# HSDL-9100.net
KiCad netlist of a schematic drawn in EAGLE
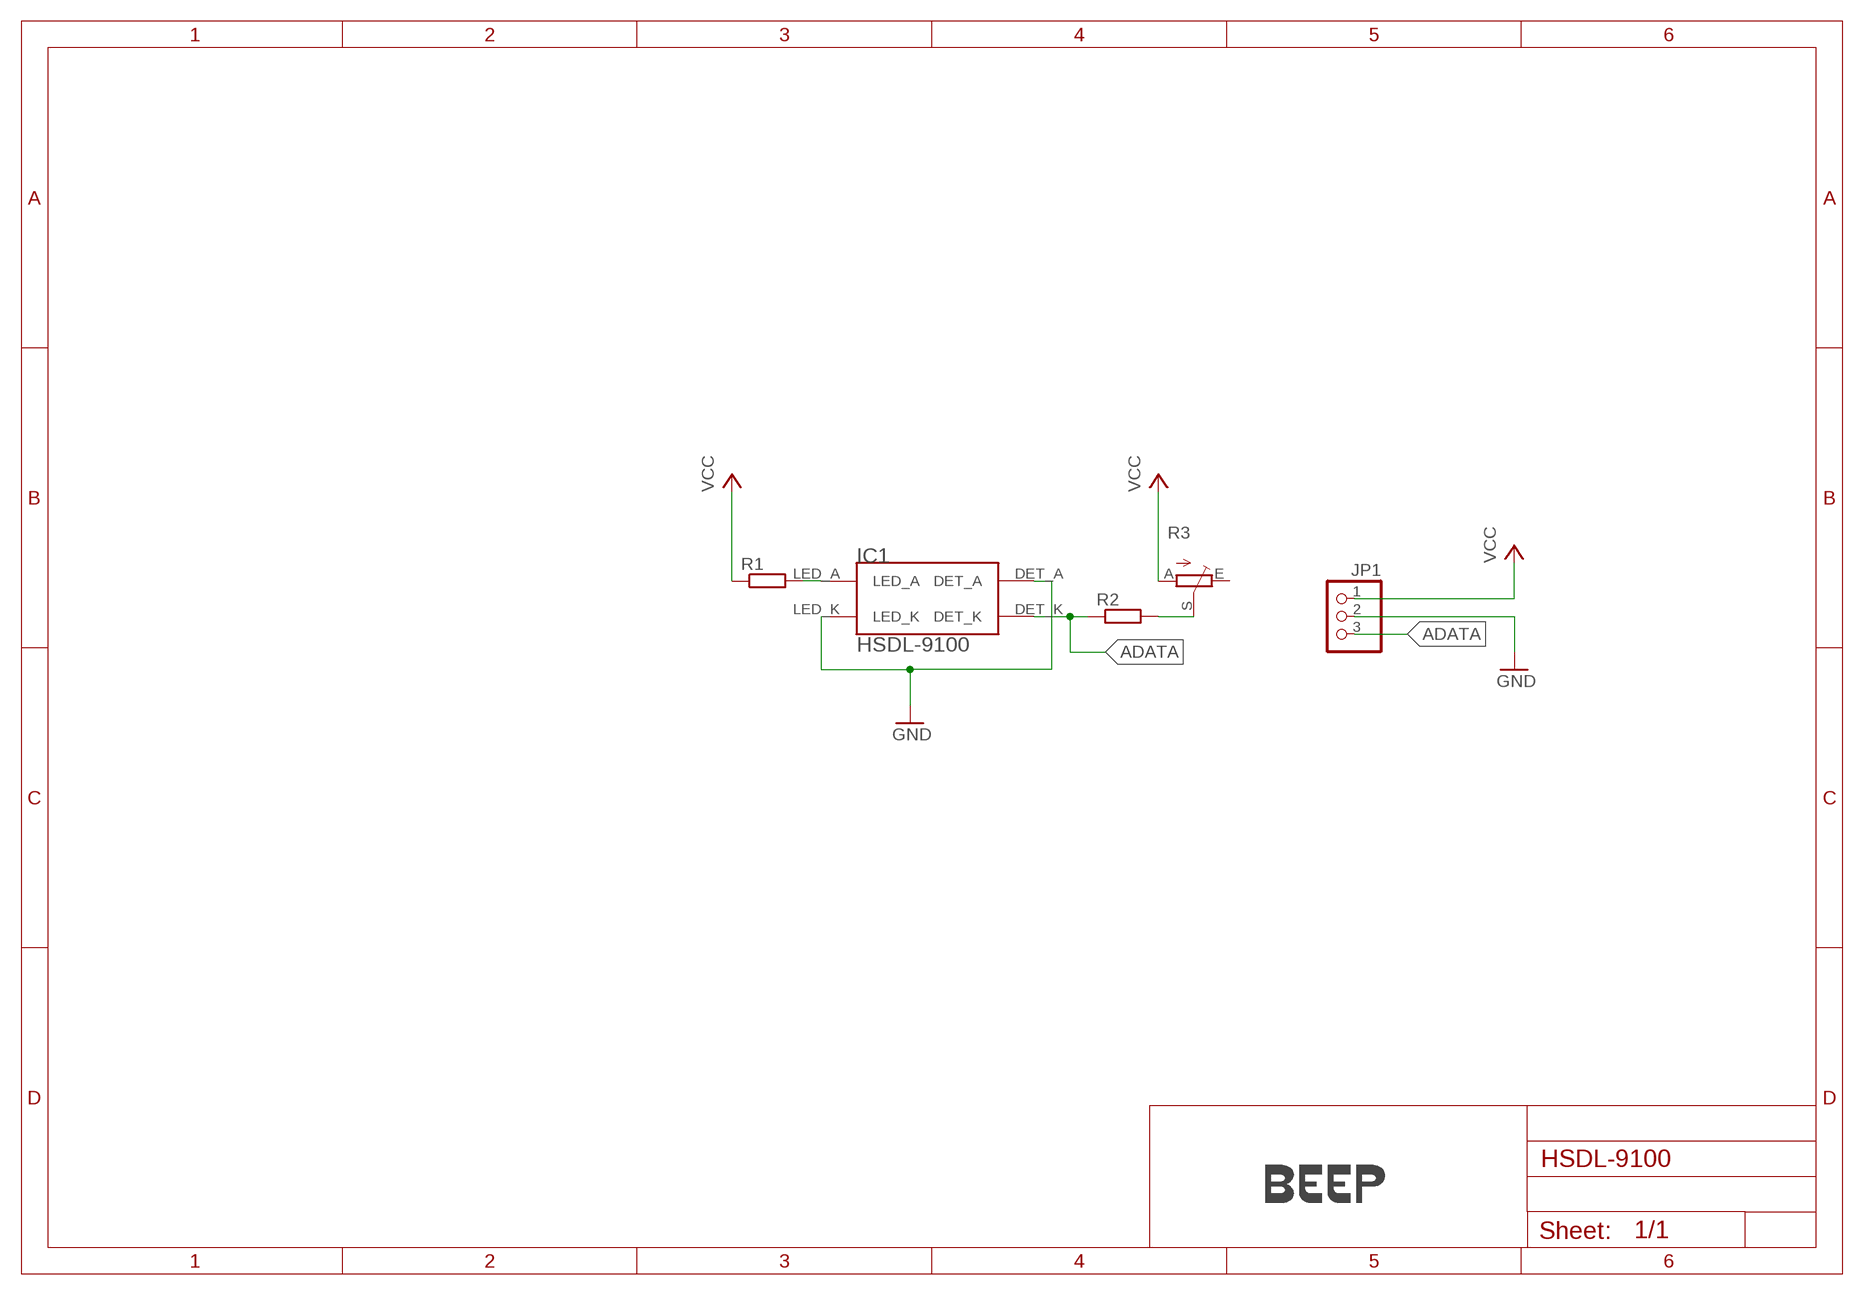
[diagram p0: schematic, sheet 1]

(export (version "E")
  (design (tool "Eeschema 10.0.6"))
  (components
    (comp (ref "IC1")
      (value "HSDL-9100")
      (footprint "eagle-import:HSDL-9100")
      (libsource (lib "eagle-import") (part "HSDL-9100"))
    )
    (comp (ref "JP1")
      (value "PINHD-1X3")
      (footprint "eagle-import:1X03")
      (libsource (lib "eagle-import") (part "PINHD-1X3"))
    )
    (comp (ref "R1")
      (value "R-EU_M0805")
      (footprint "eagle-import:M0805")
      (libsource (lib "eagle-import") (part "R-EU_M0805"))
    )
    (comp (ref "R2")
      (value "R-EU_M0805")
      (footprint "eagle-import:M0805")
      (libsource (lib "eagle-import") (part "R-EU_M0805"))
    )
    (comp (ref "R3")
      (value "TRIM_EU-B25P")
      (footprint "eagle-import:B25P")
      (libsource (lib "eagle-import") (part "TRIM_EU-B25P"))
    )
    (comp (ref "U$1")
      (value "LOGO-COPPER3")
      (footprint "eagle-import:COPPER3")
      (libsource (lib "eagle-import") (part "LOGO-COPPER3"))
    )
  )
  (nets
    (net (code "1") (name "ADATA") (class "Default")
      (node (ref "IC1") (pin "DET_K") (pinfunction "DET_K_DET_K") (pintype "bidirectional"))
      (node (ref "JP1") (pin "3") (pinfunction "3_3") (pintype "passive"))
      (node (ref "R2") (pin "1") (pinfunction "1_1") (pintype "passive"))
    )
    (net (code "2") (name "GND") (class "Default")
      (node (ref "IC1") (pin "DET_A") (pinfunction "DET_A_DET_A") (pintype "bidirectional"))
      (node (ref "IC1") (pin "LED_K") (pinfunction "LED_K_LED_K") (pintype "bidirectional"))
      (node (ref "JP1") (pin "2") (pinfunction "2_2") (pintype "passive"))
    )
    (net (code "3") (name "Net-(IC1-PadLED_A)") (class "Default")
      (node (ref "IC1") (pin "LED_A") (pinfunction "LED_A_LED_A") (pintype "bidirectional"))
      (node (ref "R1") (pin "2") (pinfunction "2_2") (pintype "passive"))
    )
    (net (code "4") (name "Net-(R2-Pad2)") (class "Default")
      (node (ref "R2") (pin "2") (pinfunction "2_2") (pintype "passive"))
      (node (ref "R3") (pin "S") (pinfunction "S_S") (pintype "passive"))
    )
    (net (code "5") (name "VCC") (class "Default")
      (node (ref "JP1") (pin "1") (pinfunction "1_1") (pintype "passive"))
      (node (ref "R1") (pin "1") (pinfunction "1_1") (pintype "passive"))
      (node (ref "R3") (pin "A") (pinfunction "A_A") (pintype "passive"))
    )
    (net (code "6") (name "unconnected-(R3-PadE)") (class "Default")
      (node (ref "R3") (pin "E") (pinfunction "E_E") (pintype "passive"))
    )
  )
)
